# pcb_univ_3-2-_1-2_-x-rev2.net
KiCad netlist of a schematic drawn in EAGLE
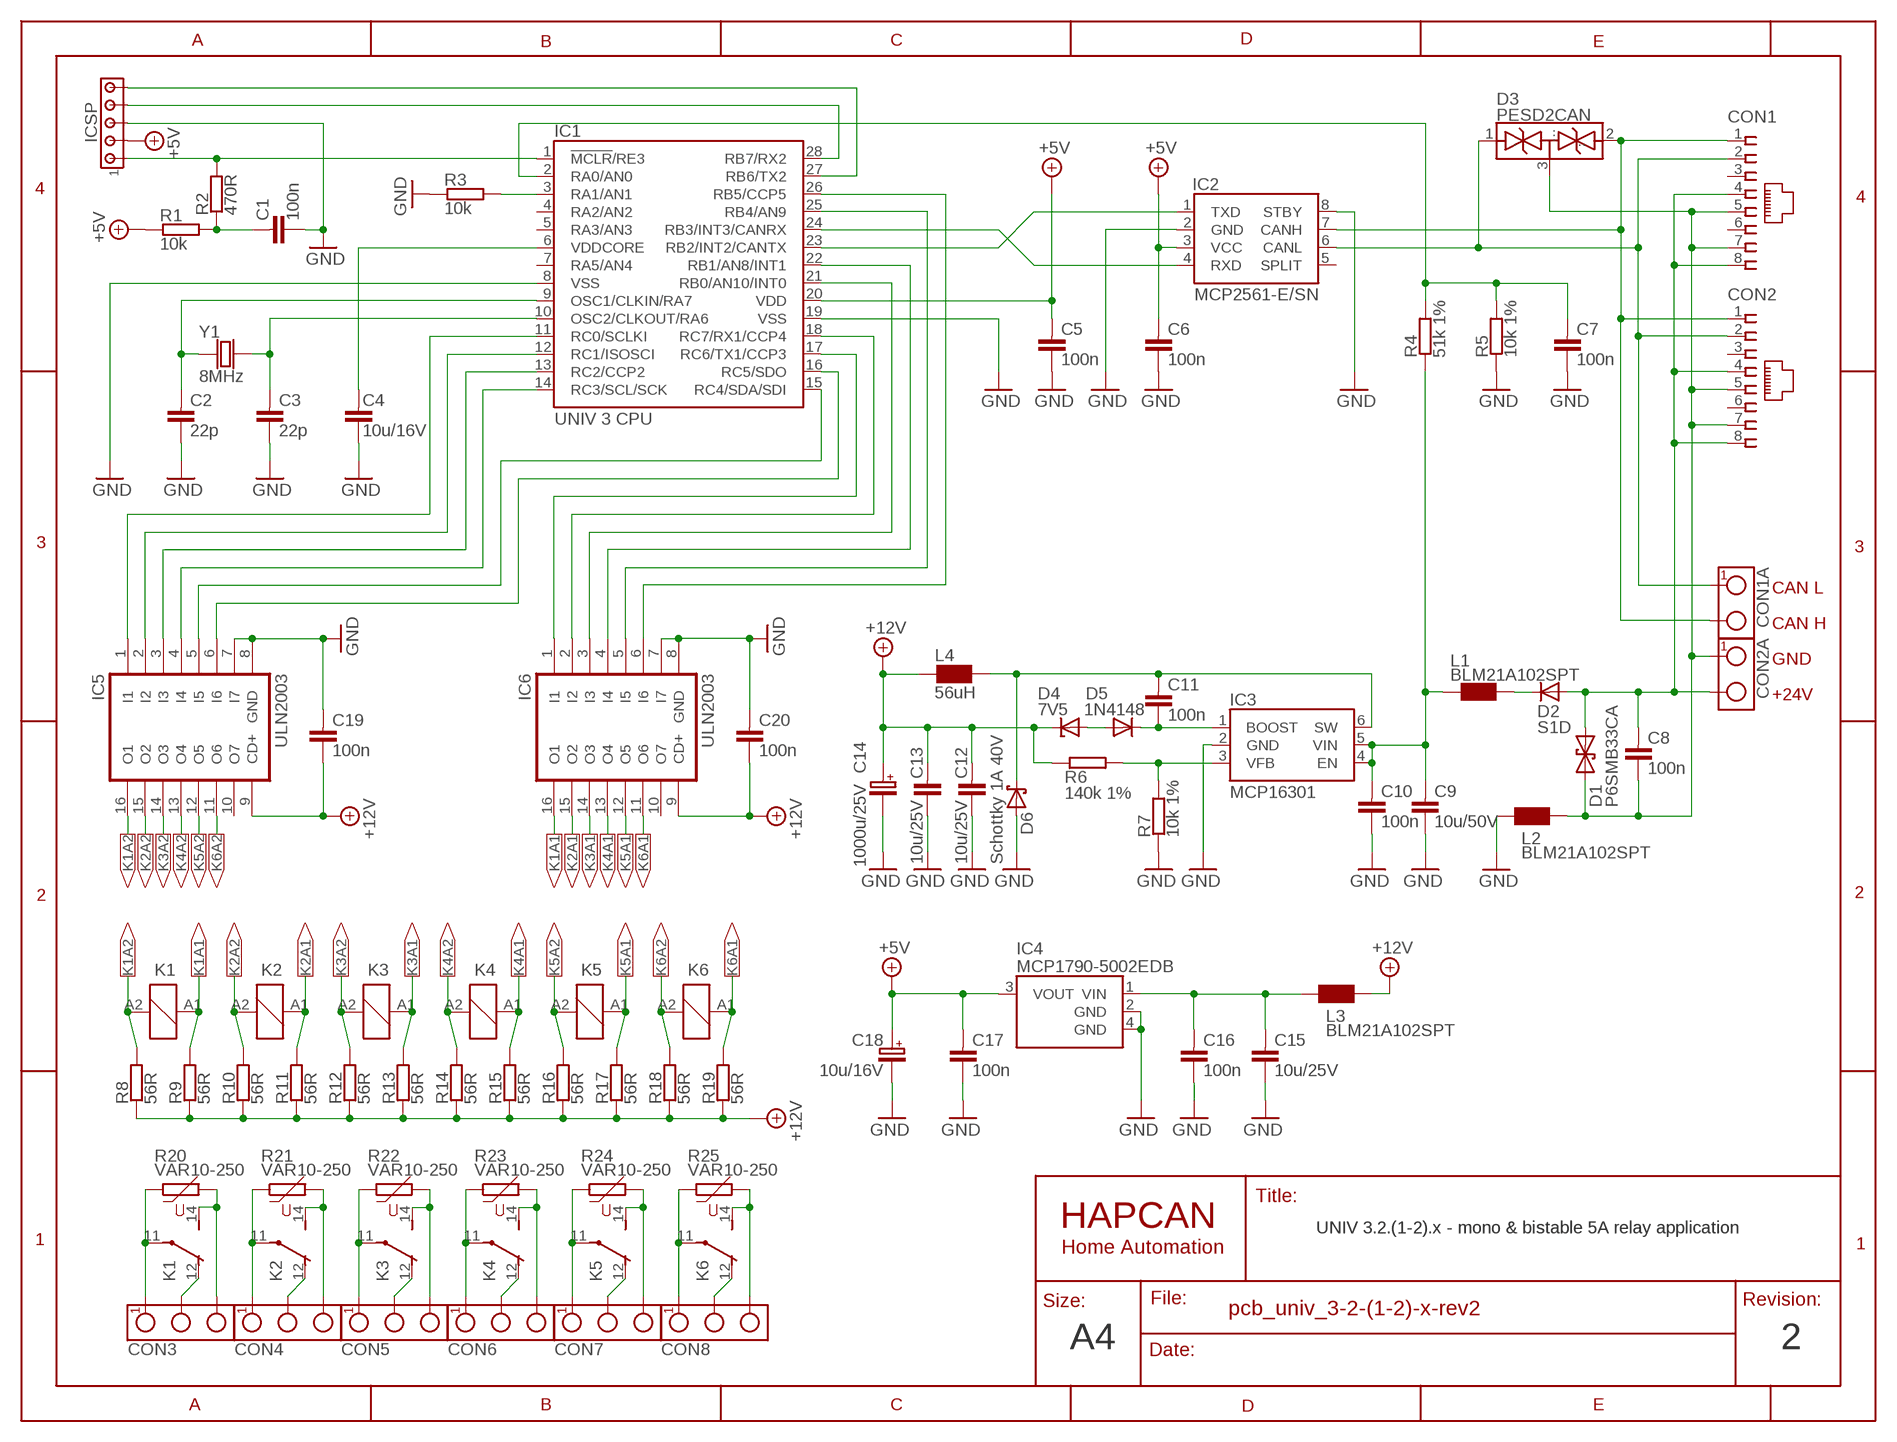
[diagram p0: schematic, sheet 1]

(export (version "E")
  (design (tool "Eeschema 10.0.6"))
  (components
    (comp (ref "C1")
      (value "100n")
      (footprint "eagle-import:0805")
      (libsource (lib "eagle-import") (part "CAPACITOR0805"))
    )
    (comp (ref "C2")
      (value "22p")
      (footprint "eagle-import:0805")
      (libsource (lib "eagle-import") (part "CAPACITOR0805"))
    )
    (comp (ref "C3")
      (value "22p")
      (footprint "eagle-import:0805")
      (libsource (lib "eagle-import") (part "CAPACITOR0805"))
    )
    (comp (ref "C4")
      (value "10u/16V")
      (footprint "eagle-import:0805")
      (libsource (lib "eagle-import") (part "CAPACITOR0805"))
    )
    (comp (ref "C5")
      (value "100n")
      (footprint "eagle-import:0805")
      (libsource (lib "eagle-import") (part "CAPACITOR0805"))
    )
    (comp (ref "C6")
      (value "100n")
      (footprint "eagle-import:0805")
      (libsource (lib "eagle-import") (part "CAPACITOR0805"))
    )
    (comp (ref "C7")
      (value "100n")
      (footprint "eagle-import:0805")
      (libsource (lib "eagle-import") (part "CAPACITOR0805"))
    )
    (comp (ref "C8")
      (value "100n")
      (footprint "eagle-import:0805")
      (libsource (lib "eagle-import") (part "CAPACITOR0805"))
    )
    (comp (ref "C9")
      (value "10u/50V")
      (footprint "eagle-import:1210")
      (libsource (lib "eagle-import") (part "CAPACITOR1210"))
    )
    (comp (ref "C10")
      (value "100n")
      (footprint "eagle-import:0805")
      (libsource (lib "eagle-import") (part "CAPACITOR0805"))
    )
    (comp (ref "C11")
      (value "100n")
      (footprint "eagle-import:0805")
      (libsource (lib "eagle-import") (part "CAPACITOR0805"))
    )
    (comp (ref "C12")
      (value "10u/25V")
      (footprint "eagle-import:1206")
      (libsource (lib "eagle-import") (part "CAPACITOR1206"))
    )
    (comp (ref "C13")
      (value "10u/25V")
      (footprint "eagle-import:1206")
      (libsource (lib "eagle-import") (part "CAPACITOR1206"))
    )
    (comp (ref "C14")
      (value "1000u/25V")
      (footprint "eagle-import:CAP-5X10.5")
      (libsource (lib "eagle-import") (part "CAPACITOR-POLARIZED-5X10.5"))
    )
    (comp (ref "C15")
      (value "10u/25V")
      (footprint "eagle-import:1206")
      (libsource (lib "eagle-import") (part "CAPACITOR1206"))
    )
    (comp (ref "C16")
      (value "100n")
      (footprint "eagle-import:0805")
      (libsource (lib "eagle-import") (part "CAPACITOR0805"))
    )
    (comp (ref "C17")
      (value "100n")
      (footprint "eagle-import:0805")
      (libsource (lib "eagle-import") (part "CAPACITOR0805"))
    )
    (comp (ref "C18")
      (value "10u/16V")
      (footprint "eagle-import:SMC_B")
      (libsource (lib "eagle-import") (part "CAPACITOR-POLARIZED-SMC_B"))
    )
    (comp (ref "C19")
      (value "100n")
      (footprint "eagle-import:0805")
      (libsource (lib "eagle-import") (part "CAPACITOR0805"))
    )
    (comp (ref "C20")
      (value "100n")
      (footprint "eagle-import:0805")
      (libsource (lib "eagle-import") (part "CAPACITOR0805"))
    )
    (comp (ref "CON1")
      (value "RJ45-SOCKET")
      (footprint "eagle-import:RJ45-PCB-SOCKET")
      (libsource (lib "eagle-import") (part "RJ45-SOCKET"))
    )
    (comp (ref "CON1A")
      (value "TERMINAL-2")
      (footprint "eagle-import:ARK2-5X10,5MM")
      (libsource (lib "eagle-import") (part "TERMINAL-2-5X10,5MM"))
    )
    (comp (ref "CON2")
      (value "RJ45-SOCKET")
      (footprint "eagle-import:RJ45-PCB-SOCKET")
      (libsource (lib "eagle-import") (part "RJ45-SOCKET"))
    )
    (comp (ref "CON2A")
      (value "TERMINAL-2")
      (footprint "eagle-import:ARK2-5X10,5MM")
      (libsource (lib "eagle-import") (part "TERMINAL-2-5X10,5MM"))
    )
    (comp (ref "CON3")
      (value "TERMINAL-3-5X10.5MM")
      (footprint "eagle-import:ARK3-5X10.5MM")
      (libsource (lib "eagle-import") (part "TERMINAL-3-5X10.5MM"))
    )
    (comp (ref "CON4")
      (value "TERMINAL-3-5X10.5MM")
      (footprint "eagle-import:ARK3-5X10.5MM")
      (libsource (lib "eagle-import") (part "TERMINAL-3-5X10.5MM"))
    )
    (comp (ref "CON5")
      (value "TERMINAL-3-5X10.5MM")
      (footprint "eagle-import:ARK3-5X10.5MM")
      (libsource (lib "eagle-import") (part "TERMINAL-3-5X10.5MM"))
    )
    (comp (ref "CON6")
      (value "TERMINAL-3-5X10.5MM")
      (footprint "eagle-import:ARK3-5X10.5MM")
      (libsource (lib "eagle-import") (part "TERMINAL-3-5X10.5MM"))
    )
    (comp (ref "CON7")
      (value "TERMINAL-3-5X10.5MM")
      (footprint "eagle-import:ARK3-5X10.5MM")
      (libsource (lib "eagle-import") (part "TERMINAL-3-5X10.5MM"))
    )
    (comp (ref "CON8")
      (value "TERMINAL-3-5X10.5MM")
      (footprint "eagle-import:ARK3-5X10.5MM")
      (libsource (lib "eagle-import") (part "TERMINAL-3-5X10.5MM"))
    )
    (comp (ref "D1")
      (value "P6SMB33CA")
      (footprint "eagle-import:DO-214_TRANSIL2")
      (libsource (lib "eagle-import") (part "DIODE_TRANSIL2"))
    )
    (comp (ref "D2")
      (value "S1D")
      (footprint "eagle-import:DO-214")
      (libsource (lib "eagle-import") (part "DIODE_DO-214"))
    )
    (comp (ref "D3")
      (value "PESD2CAN")
      (footprint "eagle-import:SOT-23")
      (libsource (lib "eagle-import") (part "PESD2CANSOT-23"))
    )
    (comp (ref "D4")
      (value "7V5")
      (footprint "eagle-import:SOD-80")
      (libsource (lib "eagle-import") (part "DIODE_ZENER_SOD-80"))
    )
    (comp (ref "D5")
      (value "1N4148")
      (footprint "eagle-import:0805")
      (libsource (lib "eagle-import") (part "DIODE_0805"))
    )
    (comp (ref "D6")
      (value "Schottky 1A 40V")
      (footprint "eagle-import:DO-214")
      (libsource (lib "eagle-import") (part "DIODE_TRANSIL1_DO214"))
    )
    (comp (ref "IC1")
      (value "UNIV 3 CPU")
      (footprint "eagle-import:UNIV3CPU")
      (libsource (lib "eagle-import") (part "UNIV3CPU-I/SO"))
    )
    (comp (ref "IC2")
      (value "MCP2561-E/SN")
      (footprint "eagle-import:SO-08")
      (libsource (lib "eagle-import") (part "MCP2561-E/SN"))
    )
    (comp (ref "IC3")
      (value "MCP16301")
      (footprint "eagle-import:SOT-23-6")
      (libsource (lib "eagle-import") (part "MCP16301SOT23-6"))
    )
    (comp (ref "IC4")
      (value "MCP1790-5002EDB")
      (footprint "eagle-import:SOT-223")
      (libsource (lib "eagle-import") (part "MCP1826SOT223-3"))
    )
    (comp (ref "IC5")
      (value "ULN2003")
      (footprint "eagle-import:SO-16")
      (libsource (lib "eagle-import") (part "ULN2003"))
    )
    (comp (ref "IC6")
      (value "ULN2003")
      (footprint "eagle-import:SO-16")
      (libsource (lib "eagle-import") (part "ULN2003"))
    )
    (comp (ref "ICSP")
      (value "HEADER5")
      (footprint "eagle-import:SIP-5")
      (libsource (lib "eagle-import") (part "HEADER5"))
    )
    (comp (ref "K1")
      (value "RELAY_PE")
      (footprint "eagle-import:RELAY_PE")
      (libsource (lib "eagle-import") (part "RELAY_PE"))
    )
    (comp (ref "K2")
      (value "RELAY_PE")
      (footprint "eagle-import:RELAY_PE")
      (libsource (lib "eagle-import") (part "RELAY_PE"))
    )
    (comp (ref "K3")
      (value "RELAY_PE")
      (footprint "eagle-import:RELAY_PE")
      (libsource (lib "eagle-import") (part "RELAY_PE"))
    )
    (comp (ref "K4")
      (value "RELAY_PE")
      (footprint "eagle-import:RELAY_PE")
      (libsource (lib "eagle-import") (part "RELAY_PE"))
    )
    (comp (ref "K5")
      (value "RELAY_PE")
      (footprint "eagle-import:RELAY_PE")
      (libsource (lib "eagle-import") (part "RELAY_PE"))
    )
    (comp (ref "K6")
      (value "RELAY_PE")
      (footprint "eagle-import:RELAY_PE")
      (libsource (lib "eagle-import") (part "RELAY_PE"))
    )
    (comp (ref "L1")
      (value "BLM21A102SPT")
      (footprint "eagle-import:0805")
      (libsource (lib "eagle-import") (part "CHOKE0805"))
    )
    (comp (ref "L2")
      (value "BLM21A102SPT")
      (footprint "eagle-import:0805")
      (libsource (lib "eagle-import") (part "CHOKE0805"))
    )
    (comp (ref "L3")
      (value "BLM21A102SPT")
      (footprint "eagle-import:0805")
      (libsource (lib "eagle-import") (part "CHOKE0805"))
    )
    (comp (ref "L4")
      (value "56uH")
      (footprint "eagle-import:CHOKE-DER0705")
      (libsource (lib "eagle-import") (part "CHOKEDER0705"))
    )
    (comp (ref "R1")
      (value "10k")
      (footprint "eagle-import:0805")
      (libsource (lib "eagle-import") (part "RESISTOR0805"))
    )
    (comp (ref "R2")
      (value "470R")
      (footprint "eagle-import:0805")
      (libsource (lib "eagle-import") (part "RESISTOR0805"))
    )
    (comp (ref "R3")
      (value "10k")
      (footprint "eagle-import:0805")
      (libsource (lib "eagle-import") (part "RESISTOR0805"))
    )
    (comp (ref "R4")
      (value "51k 1%")
      (footprint "eagle-import:0805")
      (libsource (lib "eagle-import") (part "RESISTOR0805"))
    )
    (comp (ref "R5")
      (value "10k 1%")
      (footprint "eagle-import:0805")
      (libsource (lib "eagle-import") (part "RESISTOR0805"))
    )
    (comp (ref "R6")
      (value "140k 1%")
      (footprint "eagle-import:0805")
      (libsource (lib "eagle-import") (part "RESISTOR0805"))
    )
    (comp (ref "R7")
      (value "10k 1%")
      (footprint "eagle-import:0805")
      (libsource (lib "eagle-import") (part "RESISTOR0805"))
    )
    (comp (ref "R8")
      (value "56R")
      (footprint "eagle-import:1206")
      (libsource (lib "eagle-import") (part "RESISTOR1206"))
    )
    (comp (ref "R9")
      (value "56R")
      (footprint "eagle-import:1206")
      (libsource (lib "eagle-import") (part "RESISTOR1206"))
    )
    (comp (ref "R10")
      (value "56R")
      (footprint "eagle-import:1206")
      (libsource (lib "eagle-import") (part "RESISTOR1206"))
    )
    (comp (ref "R11")
      (value "56R")
      (footprint "eagle-import:1206")
      (libsource (lib "eagle-import") (part "RESISTOR1206"))
    )
    (comp (ref "R12")
      (value "56R")
      (footprint "eagle-import:1206")
      (libsource (lib "eagle-import") (part "RESISTOR1206"))
    )
    (comp (ref "R13")
      (value "56R")
      (footprint "eagle-import:1206")
      (libsource (lib "eagle-import") (part "RESISTOR1206"))
    )
    (comp (ref "R14")
      (value "56R")
      (footprint "eagle-import:1206")
      (libsource (lib "eagle-import") (part "RESISTOR1206"))
    )
    (comp (ref "R15")
      (value "56R")
      (footprint "eagle-import:1206")
      (libsource (lib "eagle-import") (part "RESISTOR1206"))
    )
    (comp (ref "R16")
      (value "56R")
      (footprint "eagle-import:1206")
      (libsource (lib "eagle-import") (part "RESISTOR1206"))
    )
    (comp (ref "R17")
      (value "56R")
      (footprint "eagle-import:1206")
      (libsource (lib "eagle-import") (part "RESISTOR1206"))
    )
    (comp (ref "R18")
      (value "56R")
      (footprint "eagle-import:1206")
      (libsource (lib "eagle-import") (part "RESISTOR1206"))
    )
    (comp (ref "R19")
      (value "56R")
      (footprint "eagle-import:1206")
      (libsource (lib "eagle-import") (part "RESISTOR1206"))
    )
    (comp (ref "R20")
      (value "VAR10-250")
      (footprint "eagle-import:VARISTOR1")
      (libsource (lib "eagle-import") (part "VARISTOR7.5MM-1"))
    )
    (comp (ref "R21")
      (value "VAR10-250")
      (footprint "eagle-import:VARISTOR1")
      (libsource (lib "eagle-import") (part "VARISTOR7.5MM-1"))
    )
    (comp (ref "R22")
      (value "VAR10-250")
      (footprint "eagle-import:VARISTOR1")
      (libsource (lib "eagle-import") (part "VARISTOR7.5MM-1"))
    )
    (comp (ref "R23")
      (value "VAR10-250")
      (footprint "eagle-import:VARISTOR1")
      (libsource (lib "eagle-import") (part "VARISTOR7.5MM-1"))
    )
    (comp (ref "R24")
      (value "VAR10-250")
      (footprint "eagle-import:VARISTOR1")
      (libsource (lib "eagle-import") (part "VARISTOR7.5MM-1"))
    )
    (comp (ref "R25")
      (value "VAR10-250")
      (footprint "eagle-import:VARISTOR1")
      (libsource (lib "eagle-import") (part "VARISTOR7.5MM-1"))
    )
    (comp (ref "Y1")
      (value "8MHz")
      (footprint "eagle-import:CRYSTAL-HC49V")
      (libsource (lib "eagle-import") (part "CRYSTAL-HC49V"))
    )
  )
  (nets
    (net (code "1") (name "+5V") (class "Default")
      (node (ref "C17") (pin "1") (pinfunction "1_1") (pintype "passive"))
      (node (ref "C18") (pin "+") (pinfunction "1_+") (pintype "passive"))
      (node (ref "C5") (pin "1") (pinfunction "1_1") (pintype "passive"))
      (node (ref "C6") (pin "1") (pinfunction "1_1") (pintype "passive"))
      (node (ref "IC1") (pin "20") (pinfunction "VDD_20") (pintype "bidirectional"))
      (node (ref "IC2") (pin "3") (pinfunction "VCC_3") (pintype "bidirectional"))
      (node (ref "IC4") (pin "3") (pinfunction "VOUT_3") (pintype "bidirectional"))
      (node (ref "ICSP") (pin "2") (pinfunction "2_2") (pintype "passive"))
      (node (ref "R1") (pin "1") (pinfunction "1_1") (pintype "passive"))
    )
    (net (code "2") (name "+12V") (class "Default")
      (node (ref "C12") (pin "1") (pinfunction "1_1") (pintype "passive"))
      (node (ref "C13") (pin "1") (pinfunction "1_1") (pintype "passive"))
      (node (ref "C14") (pin "+") (pinfunction "1_+") (pintype "passive"))
      (node (ref "C19") (pin "2") (pinfunction "2_2") (pintype "passive"))
      (node (ref "C20") (pin "2") (pinfunction "2_2") (pintype "passive"))
      (node (ref "D4") (pin "C") (pinfunction "C_C") (pintype "passive"))
      (node (ref "IC5") (pin "9") (pinfunction "CD+_9") (pintype "passive"))
      (node (ref "IC6") (pin "9") (pinfunction "CD+_9") (pintype "passive"))
      (node (ref "L3") (pin "2") (pinfunction "2_2") (pintype "passive"))
      (node (ref "L4") (pin "1") (pinfunction "1_1") (pintype "passive"))
      (node (ref "R10") (pin "1") (pinfunction "1_1") (pintype "passive"))
      (node (ref "R11") (pin "1") (pinfunction "1_1") (pintype "passive"))
      (node (ref "R12") (pin "1") (pinfunction "1_1") (pintype "passive"))
      (node (ref "R13") (pin "1") (pinfunction "1_1") (pintype "passive"))
      (node (ref "R14") (pin "1") (pinfunction "1_1") (pintype "passive"))
      (node (ref "R15") (pin "1") (pinfunction "1_1") (pintype "passive"))
      (node (ref "R16") (pin "1") (pinfunction "1_1") (pintype "passive"))
      (node (ref "R17") (pin "1") (pinfunction "1_1") (pintype "passive"))
      (node (ref "R18") (pin "1") (pinfunction "1_1") (pintype "passive"))
      (node (ref "R19") (pin "1") (pinfunction "1_1") (pintype "passive"))
      (node (ref "R6") (pin "1") (pinfunction "1_1") (pintype "passive"))
      (node (ref "R8") (pin "1") (pinfunction "1_1") (pintype "passive"))
      (node (ref "R9") (pin "1") (pinfunction "1_1") (pintype "passive"))
    )
    (net (code "3") (name "/K1A1") (class "Default")
      (node (ref "IC6") (pin "16") (pinfunction "O1_16") (pintype "open_collector"))
      (node (ref "K1") (pin "A1") (pinfunction "1_A1") (pintype "passive"))
      (node (ref "R9") (pin "2") (pinfunction "2_2") (pintype "passive"))
    )
    (net (code "4") (name "/K1A2") (class "Default")
      (node (ref "IC5") (pin "16") (pinfunction "O1_16") (pintype "open_collector"))
      (node (ref "K1") (pin "A2") (pinfunction "2_A2") (pintype "passive"))
      (node (ref "R8") (pin "2") (pinfunction "2_2") (pintype "passive"))
    )
    (net (code "5") (name "/K2A1") (class "Default")
      (node (ref "IC6") (pin "15") (pinfunction "O2_15") (pintype "open_collector"))
      (node (ref "K2") (pin "A1") (pinfunction "1_A1") (pintype "passive"))
      (node (ref "R11") (pin "2") (pinfunction "2_2") (pintype "passive"))
    )
    (net (code "6") (name "/K2A2") (class "Default")
      (node (ref "IC5") (pin "15") (pinfunction "O2_15") (pintype "open_collector"))
      (node (ref "K2") (pin "A2") (pinfunction "2_A2") (pintype "passive"))
      (node (ref "R10") (pin "2") (pinfunction "2_2") (pintype "passive"))
    )
    (net (code "7") (name "/K3A1") (class "Default")
      (node (ref "IC6") (pin "14") (pinfunction "O3_14") (pintype "open_collector"))
      (node (ref "K3") (pin "A1") (pinfunction "1_A1") (pintype "passive"))
      (node (ref "R13") (pin "2") (pinfunction "2_2") (pintype "passive"))
    )
    (net (code "8") (name "/K3A2") (class "Default")
      (node (ref "IC5") (pin "14") (pinfunction "O3_14") (pintype "open_collector"))
      (node (ref "K3") (pin "A2") (pinfunction "2_A2") (pintype "passive"))
      (node (ref "R12") (pin "2") (pinfunction "2_2") (pintype "passive"))
    )
    (net (code "9") (name "/K4A1") (class "Default")
      (node (ref "IC6") (pin "13") (pinfunction "O4_13") (pintype "open_collector"))
      (node (ref "K4") (pin "A1") (pinfunction "1_A1") (pintype "passive"))
      (node (ref "R15") (pin "2") (pinfunction "2_2") (pintype "passive"))
    )
    (net (code "10") (name "/K4A2") (class "Default")
      (node (ref "IC5") (pin "13") (pinfunction "O4_13") (pintype "open_collector"))
      (node (ref "K4") (pin "A2") (pinfunction "2_A2") (pintype "passive"))
      (node (ref "R14") (pin "2") (pinfunction "2_2") (pintype "passive"))
    )
    (net (code "11") (name "/K5A1") (class "Default")
      (node (ref "IC6") (pin "12") (pinfunction "O5_12") (pintype "open_collector"))
      (node (ref "K5") (pin "A1") (pinfunction "1_A1") (pintype "passive"))
      (node (ref "R17") (pin "2") (pinfunction "2_2") (pintype "passive"))
    )
    (net (code "12") (name "/K5A2") (class "Default")
      (node (ref "IC5") (pin "12") (pinfunction "O5_12") (pintype "open_collector"))
      (node (ref "K5") (pin "A2") (pinfunction "2_A2") (pintype "passive"))
      (node (ref "R16") (pin "2") (pinfunction "2_2") (pintype "passive"))
    )
    (net (code "13") (name "/K6A1") (class "Default")
      (node (ref "IC6") (pin "11") (pinfunction "O6_11") (pintype "open_collector"))
      (node (ref "K6") (pin "A1") (pinfunction "1_A1") (pintype "passive"))
      (node (ref "R19") (pin "2") (pinfunction "2_2") (pintype "passive"))
    )
    (net (code "14") (name "/K6A2") (class "Default")
      (node (ref "IC5") (pin "11") (pinfunction "O6_11") (pintype "open_collector"))
      (node (ref "K6") (pin "A2") (pinfunction "2_A2") (pintype "passive"))
      (node (ref "R18") (pin "2") (pinfunction "2_2") (pintype "passive"))
    )
    (net (code "15") (name "GND") (class "Default")
      (node (ref "C1") (pin "2") (pinfunction "2_2") (pintype "passive"))
      (node (ref "C10") (pin "2") (pinfunction "2_2") (pintype "passive"))
      (node (ref "C12") (pin "2") (pinfunction "2_2") (pintype "passive"))
      (node (ref "C13") (pin "2") (pinfunction "2_2") (pintype "passive"))
      (node (ref "C14") (pin "-") (pinfunction "2_-") (pintype "passive"))
      (node (ref "C15") (pin "2") (pinfunction "2_2") (pintype "passive"))
      (node (ref "C16") (pin "2") (pinfunction "2_2") (pintype "passive"))
      (node (ref "C17") (pin "2") (pinfunction "2_2") (pintype "passive"))
      (node (ref "C18") (pin "-") (pinfunction "2_-") (pintype "passive"))
      (node (ref "C19") (pin "1") (pinfunction "1_1") (pintype "passive"))
      (node (ref "C2") (pin "2") (pinfunction "2_2") (pintype "passive"))
      (node (ref "C20") (pin "1") (pinfunction "1_1") (pintype "passive"))
      (node (ref "C3") (pin "2") (pinfunction "2_2") (pintype "passive"))
      (node (ref "C4") (pin "2") (pinfunction "2_2") (pintype "passive"))
      (node (ref "C5") (pin "2") (pinfunction "2_2") (pintype "passive"))
      (node (ref "C6") (pin "2") (pinfunction "2_2") (pintype "passive"))
      (node (ref "C7") (pin "2") (pinfunction "2_2") (pintype "passive"))
      (node (ref "C9") (pin "2") (pinfunction "2_2") (pintype "passive"))
      (node (ref "D6") (pin "A") (pinfunction "A_A") (pintype "passive"))
      (node (ref "IC1") (pin "19") (pinfunction "VSS_19") (pintype "bidirectional"))
      (node (ref "IC1") (pin "8") (pinfunction "VSS_8") (pintype "bidirectional"))
      (node (ref "IC2") (pin "2") (pinfunction "GND_2") (pintype "bidirectional"))
      (node (ref "IC2") (pin "8") (pinfunction "STBY_8") (pintype "bidirectional"))
      (node (ref "IC3") (pin "2") (pinfunction "GND_2") (pintype "bidirectional"))
      (node (ref "IC4") (pin "2") (pinfunction "GND_2") (pintype "bidirectional"))
      (node (ref "IC4") (pin "4") (pinfunction "GND_4") (pintype "bidirectional"))
      (node (ref "IC5") (pin "7") (pinfunction "I7_7") (pintype "input"))
      (node (ref "IC5") (pin "8") (pinfunction "GND_8") (pintype "power_in"))
      (node (ref "IC6") (pin "7") (pinfunction "I7_7") (pintype "input"))
      (node (ref "IC6") (pin "8") (pinfunction "GND_8") (pintype "power_in"))
      (node (ref "ICSP") (pin "3") (pinfunction "3_3") (pintype "passive"))
      (node (ref "L2") (pin "1") (pinfunction "1_1") (pintype "passive"))
      (node (ref "R3") (pin "1") (pinfunction "1_1") (pintype "passive"))
      (node (ref "R5") (pin "1") (pinfunction "1_1") (pintype "passive"))
      (node (ref "R7") (pin "1") (pinfunction "1_1") (pintype "passive"))
    )
    (net (code "16") (name "Net-(C1-Pad1)") (class "Default")
      (node (ref "C1") (pin "1") (pinfunction "1_1") (pintype "passive"))
      (node (ref "R1") (pin "2") (pinfunction "2_2") (pintype "passive"))
      (node (ref "R2") (pin "1") (pinfunction "1_1") (pintype "passive"))
    )
    (net (code "17") (name "Net-(D1-1)") (class "Default")
      (node (ref "C8") (pin "2") (pinfunction "2_2") (pintype "passive"))
      (node (ref "CON1") (pin "5") (pinfunction "5_5") (pintype "passive"))
      (node (ref "CON1") (pin "7") (pinfunction "7_7") (pintype "passive"))
      (node (ref "CON2") (pin "5") (pinfunction "5_5") (pintype "passive"))
      (node (ref "CON2") (pin "7") (pinfunction "7_7") (pintype "passive"))
      (node (ref "CON2A") (pin "1") (pinfunction "1_1") (pintype "passive"))
      (node (ref "D1") (pin "A") (pinfunction "1_A") (pintype "passive"))
      (node (ref "D3") (pin "3") (pinfunction "..._3") (pintype "bidirectional"))
      (node (ref "L2") (pin "2") (pinfunction "2_2") (pintype "passive"))
    )
    (net (code "18") (name "Net-(D1-2)") (class "Default")
      (node (ref "C8") (pin "1") (pinfunction "1_1") (pintype "passive"))
      (node (ref "CON1") (pin "4") (pinfunction "4_4") (pintype "passive"))
      (node (ref "CON1") (pin "8") (pinfunction "8_8") (pintype "passive"))
      (node (ref "CON2") (pin "4") (pinfunction "4_4") (pintype "passive"))
      (node (ref "CON2") (pin "8") (pinfunction "8_8") (pintype "passive"))
      (node (ref "CON2A") (pin "2") (pinfunction "2_2") (pintype "passive"))
      (node (ref "D1") (pin "C") (pinfunction "2_C") (pintype "passive"))
      (node (ref "D2") (pin "A") (pinfunction "A_A") (pintype "passive"))
    )
    (net (code "19") (name "Net-(D2-PadC)") (class "Default")
      (node (ref "D2") (pin "C") (pinfunction "C_C") (pintype "passive"))
      (node (ref "L1") (pin "2") (pinfunction "2_2") (pintype "passive"))
    )
    (net (code "20") (name "Net-(D3-.)") (class "Default")
      (node (ref "CON1") (pin "2") (pinfunction "2_2") (pintype "passive"))
      (node (ref "CON1A") (pin "1") (pinfunction "1_1") (pintype "passive"))
      (node (ref "CON2") (pin "2") (pinfunction "2_2") (pintype "passive"))
      (node (ref "D3") (pin "1") (pinfunction "._1") (pintype "bidirectional"))
      (node (ref "IC2") (pin "6") (pinfunction "CANL_6") (pintype "bidirectional"))
    )
    (net (code "21") (name "Net-(D3-..)") (class "Default")
      (node (ref "CON1") (pin "1") (pinfunction "1_1") (pintype "passive"))
      (node (ref "CON1A") (pin "2") (pinfunction "2_2") (pintype "passive"))
      (node (ref "CON2") (pin "1") (pinfunction "1_1") (pintype "passive"))
      (node (ref "D3") (pin "2") (pinfunction ".._2") (pintype "bidirectional"))
      (node (ref "IC2") (pin "7") (pinfunction "CANH_7") (pintype "bidirectional"))
    )
    (net (code "22") (name "Net-(D5-A)") (class "Default")
      (node (ref "D4") (pin "A") (pinfunction "A_A") (pintype "passive"))
      (node (ref "D5") (pin "2") (pinfunction "A_2") (pintype "passive"))
    )
    (net (code "23") (name "Net-(D5-C)") (class "Default")
      (node (ref "C11") (pin "2") (pinfunction "2_2") (pintype "passive"))
      (node (ref "D5") (pin "1") (pinfunction "C_1") (pintype "passive"))
      (node (ref "IC3") (pin "1") (pinfunction "BOOST_1") (pintype "bidirectional"))
    )
    (net (code "24") (name "Net-(IC1-OSC1{slash}CLKIN{slash}RA7)") (class "Default")
      (node (ref "C2") (pin "1") (pinfunction "1_1") (pintype "passive"))
      (node (ref "IC1") (pin "9") (pinfunction "OSC1/CLKIN/RA7_9") (pintype "bidirectional"))
      (node (ref "Y1") (pin "1") (pinfunction "1_1") (pintype "passive"))
    )
    (net (code "25") (name "Net-(IC1-OSC2{slash}CLKOUT{slash}RA6)") (class "Default")
      (node (ref "C3") (pin "1") (pinfunction "1_1") (pintype "passive"))
      (node (ref "IC1") (pin "10") (pinfunction "OSC2/CLKOUT/RA6_10") (pintype "bidirectional"))
      (node (ref "Y1") (pin "2") (pinfunction "2_2") (pintype "passive"))
    )
    (net (code "26") (name "Net-(IC1-RA0{slash}AN0)") (class "Default")
      (node (ref "C7") (pin "1") (pinfunction "1_1") (pintype "passive"))
      (node (ref "IC1") (pin "2") (pinfunction "RA0/AN0_2") (pintype "bidirectional"))
      (node (ref "R4") (pin "2") (pinfunction "2_2") (pintype "passive"))
      (node (ref "R5") (pin "2") (pinfunction "2_2") (pintype "passive"))
    )
    (net (code "27") (name "Net-(IC1-RA1{slash}AN1)") (class "Default")
      (node (ref "IC1") (pin "3") (pinfunction "RA1/AN1_3") (pintype "bidirectional"))
      (node (ref "R3") (pin "2") (pinfunction "2_2") (pintype "passive"))
    )
    (net (code "28") (name "Net-(IC1-RB0{slash}AN10{slash}INT0)") (class "Default")
      (node (ref "IC1") (pin "21") (pinfunction "RB0/AN10/INT0_21") (pintype "bidirectional"))
      (node (ref "IC6") (pin "3") (pinfunction "I3_3") (pintype "input"))
    )
    (net (code "29") (name "Net-(IC1-RB1{slash}AN8{slash}INT1)") (class "Default")
      (node (ref "IC1") (pin "22") (pinfunction "RB1/AN8/INT1_22") (pintype "bidirectional"))
      (node (ref "IC6") (pin "4") (pinfunction "I4_4") (pintype "input"))
    )
    (net (code "30") (name "Net-(IC1-RB2{slash}INT2{slash}CANTX)") (class "Default")
      (node (ref "IC1") (pin "23") (pinfunction "RB2/INT2/CANTX_23") (pintype "bidirectional"))
      (node (ref "IC2") (pin "1") (pinfunction "TXD_1") (pintype "bidirectional"))
    )
    (net (code "31") (name "Net-(IC1-RB3{slash}INT3{slash}CANRX)") (class "Default")
      (node (ref "IC1") (pin "24") (pinfunction "RB3/INT3/CANRX_24") (pintype "bidirectional"))
      (node (ref "IC2") (pin "4") (pinfunction "RXD_4") (pintype "bidirectional"))
    )
    (net (code "32") (name "Net-(IC1-RB4{slash}AN9)") (class "Default")
      (node (ref "IC1") (pin "25") (pinfunction "RB4/AN9_25") (pintype "bidirectional"))
      (node (ref "IC6") (pin "5") (pinfunction "I5_5") (pintype "input"))
    )
    (net (code "33") (name "Net-(IC1-RB5{slash}CCP5)") (class "Default")
      (node (ref "IC1") (pin "26") (pinfunction "RB5/CCP5_26") (pintype "bidirectional"))
      (node (ref "IC6") (pin "6") (pinfunction "I6_6") (pintype "input"))
    )
    (net (code "34") (name "Net-(IC1-RB6{slash}TX2)") (class "Default")
      (node (ref "IC1") (pin "27") (pinfunction "RB6/TX2_27") (pintype "bidirectional"))
      (node (ref "ICSP") (pin "5") (pinfunction "5_5") (pintype "passive"))
    )
    (net (code "35") (name "Net-(IC1-RB7{slash}RX2)") (class "Default")
      (node (ref "IC1") (pin "28") (pinfunction "RB7/RX2_28") (pintype "bidirectional"))
      (node (ref "ICSP") (pin "4") (pinfunction "4_4") (pintype "passive"))
    )
    (net (code "36") (name "Net-(IC1-RC0{slash}SCLKI)") (class "Default")
      (node (ref "IC1") (pin "11") (pinfunction "RC0/SCLKI_11") (pintype "bidirectional"))
      (node (ref "IC5") (pin "1") (pinfunction "I1_1") (pintype "input"))
    )
    (net (code "37") (name "Net-(IC1-RC1{slash}ISOSCI)") (class "Default")
      (node (ref "IC1") (pin "12") (pinfunction "RC1/ISOSCI_12") (pintype "bidirectional"))
      (node (ref "IC5") (pin "2") (pinfunction "I2_2") (pintype "input"))
    )
    (net (code "38") (name "Net-(IC1-RC2{slash}CCP2)") (class "Default")
      (node (ref "IC1") (pin "13") (pinfunction "RC2/CCP2_13") (pintype "bidirectional"))
      (node (ref "IC5") (pin "3") (pinfunction "I3_3") (pintype "input"))
    )
    (net (code "39") (name "Net-(IC1-RC3{slash}SCL{slash}SCK)") (class "Default")
      (node (ref "IC1") (pin "14") (pinfunction "RC3/SCL/SCK_14") (pintype "bidirectional"))
      (node (ref "IC5") (pin "4") (pinfunction "I4_4") (pintype "input"))
    )
    (net (code "40") (name "Net-(IC1-RC4{slash}SDA{slash}SDI)") (class "Default")
      (node (ref "IC1") (pin "15") (pinfunction "RC4/SDA/SDI_15") (pintype "bidirectional"))
      (node (ref "IC5") (pin "5") (pinfunction "I5_5") (pintype "input"))
    )
    (net (code "41") (name "Net-(IC1-RC5{slash}SDO)") (class "Default")
      (node (ref "IC1") (pin "16") (pinfunction "RC5/SDO_16") (pintype "bidirectional"))
      (node (ref "IC5") (pin "6") (pinfunction "I6_6") (pintype "input"))
    )
    (net (code "42") (name "Net-(IC1-RC6{slash}TX1{slash}CCP3)") (class "Default")
      (node (ref "IC1") (pin "17") (pinfunction "RC6/TX1/CCP3_17") (pintype "bidirectional"))
      (node (ref "IC6") (pin "1") (pinfunction "I1_1") (pintype "input"))
    )
    (net (code "43") (name "Net-(IC1-RC7{slash}RX1{slash}CCP4)") (class "Default")
      (node (ref "IC1") (pin "18") (pinfunction "RC7/RX1/CCP4_18") (pintype "bidirectional"))
      (node (ref "IC6") (pin "2") (pinfunction "I2_2") (pintype "input"))
    )
    (net (code "44") (name "Net-(IC1-VDDCORE)") (class "Default")
      (node (ref "C4") (pin "1") (pinfunction "1_1") (pintype "passive"))
      (node (ref "IC1") (pin "6") (pinfunction "VDDCORE_6") (pintype "bidirectional"))
    )
    (net (code "45") (name "Net-(IC1-~{MCLR}{slash}RE3)") (class "Default")
      (node (ref "IC1") (pin "1") (pinfunction "~{MCLR}/RE3_1") (pintype "bidirectional"))
      (node (ref "ICSP") (pin "1") (pinfunction "1_1") (pintype "passive"))
      (node (ref "R2") (pin "2") (pinfunction "2_2") (pintype "passive"))
    )
    (net (code "46") (name "Net-(IC3-EN)") (class "Default")
      (node (ref "C10") (pin "1") (pinfunction "1_1") (pintype "passive"))
      (node (ref "C9") (pin "1") (pinfunction "1_1") (pintype "passive"))
      (node (ref "IC3") (pin "4") (pinfunction "EN_4") (pintype "bidirectional"))
      (node (ref "IC3") (pin "5") (pinfunction "VIN_5") (pintype "bidirectional"))
      (node (ref "L1") (pin "1") (pinfunction "1_1") (pintype "passive"))
      (node (ref "R4") (pin "1") (pinfunction "1_1") (pintype "passive"))
    )
    (net (code "47") (name "Net-(IC3-SW)") (class "Default")
      (node (ref "C11") (pin "1") (pinfunction "1_1") (pintype "passive"))
      (node (ref "D6") (pin "C") (pinfunction "C_C") (pintype "passive"))
      (node (ref "IC3") (pin "6") (pinfunction "SW_6") (pintype "bidirectional"))
      (node (ref "L4") (pin "2") (pinfunction "2_2") (pintype "passive"))
    )
    (net (code "48") (name "Net-(IC3-VFB)") (class "Default")
      (node (ref "IC3") (pin "3") (pinfunction "VFB_3") (pintype "bidirectional"))
      (node (ref "R6") (pin "2") (pinfunction "2_2") (pintype "passive"))
      (node (ref "R7") (pin "2") (pinfunction "2_2") (pintype "passive"))
    )
    (net (code "49") (name "Net-(IC4-VIN)") (class "Default")
      (node (ref "C15") (pin "1") (pinfunction "1_1") (pintype "passive"))
      (node (ref "C16") (pin "1") (pinfunction "1_1") (pintype "passive"))
      (node (ref "IC4") (pin "1") (pinfunction "VIN_1") (pintype "bidirectional"))
      (node (ref "L3") (pin "1") (pinfunction "1_1") (pintype "passive"))
    )
    (net (code "50") (name "Net-(K1B-COM)") (class "Default")
      (node (ref "CON3") (pin "1") (pinfunction "1_1") (pintype "passive"))
      (node (ref "K1") (pin "11") (pinfunction "COM_11") (pintype "passive"))
      (node (ref "R20") (pin "1") (pinfunction "1_1") (pintype "passive"))
    )
    (net (code "51") (name "Net-(K1B-NC)") (class "Default")
      (node (ref "CON3") (pin "2") (pinfunction "2_2") (pintype "passive"))
      (node (ref "K1") (pin "12") (pinfunction "NC_12") (pintype "passive"))
    )
    (net (code "52") (name "Net-(K1B-NO)") (class "Default")
      (node (ref "CON3") (pin "3") (pinfunction "3_3") (pintype "passive"))
      (node (ref "K1") (pin "14") (pinfunction "NO_14") (pintype "passive"))
      (node (ref "R20") (pin "2") (pinfunction "2_2") (pintype "passive"))
    )
    (net (code "53") (name "Net-(K2B-COM)") (class "Default")
      (node (ref "CON4") (pin "1") (pinfunction "1_1") (pintype "passive"))
      (node (ref "K2") (pin "11") (pinfunction "COM_11") (pintype "passive"))
      (node (ref "R21") (pin "1") (pinfunction "1_1") (pintype "passive"))
    )
    (net (code "54") (name "Net-(K2B-NC)") (class "Default")
      (node (ref "CON4") (pin "2") (pinfunction "2_2") (pintype "passive"))
      (node (ref "K2") (pin "12") (pinfunction "NC_12") (pintype "passive"))
    )
    (net (code "55") (name "Net-(K2B-NO)") (class "Default")
      (node (ref "CON4") (pin "3") (pinfunction "3_3") (pintype "passive"))
      (node (ref "K2") (pin "14") (pinfunction "NO_14") (pintype "passive"))
      (node (ref "R21") (pin "2") (pinfunction "2_2") (pintype "passive"))
    )
    (net (code "56") (name "Net-(K3B-COM)") (class "Default")
      (node (ref "CON5") (pin "1") (pinfunction "1_1") (pintype "passive"))
      (node (ref "K3") (pin "11") (pinfunction "COM_11") (pintype "passive"))
      (node (ref "R22") (pin "1") (pinfunction "1_1") (pintype "passive"))
    )
    (net (code "57") (name "Net-(K3B-NC)") (class "Default")
      (node (ref "CON5") (pin "2") (pinfunction "2_2") (pintype "passive"))
      (node (ref "K3") (pin "12") (pinfunction "NC_12") (pintype "passive"))
    )
    (net (code "58") (name "Net-(K3B-NO)") (class "Default")
      (node (ref "CON5") (pin "3") (pinfunction "3_3") (pintype "passive"))
      (node (ref "K3") (pin "14") (pinfunction "NO_14") (pintype "passive"))
      (node (ref "R22") (pin "2") (pinfunction "2_2") (pintype "passive"))
    )
    (net (code "59") (name "Net-(K4B-COM)") (class "Default")
      (node (ref "CON6") (pin "1") (pinfunction "1_1") (pintype "passive"))
      (node (ref "K4") (pin "11") (pinfunction "COM_11") (pintype "passive"))
      (node (ref "R23") (pin "1") (pinfunction "1_1") (pintype "passive"))
    )
    (net (code "60") (name "Net-(K4B-NC)") (class "Default")
      (node (ref "CON6") (pin "2") (pinfunction "2_2") (pintype "passive"))
      (node (ref "K4") (pin "12") (pinfunction "NC_12") (pintype "passive"))
    )
    (net (code "61") (name "Net-(K4B-NO)") (class "Default")
      (node (ref "CON6") (pin "3") (pinfunction "3_3") (pintype "passive"))
      (node (ref "K4") (pin "14") (pinfunction "NO_14") (pintype "passive"))
      (node (ref "R23") (pin "2") (pinfunction "2_2") (pintype "passive"))
    )
    (net (code "62") (name "Net-(K5B-COM)") (class "Default")
      (node (ref "CON7") (pin "1") (pinfunction "1_1") (pintype "passive"))
      (node (ref "K5") (pin "11") (pinfunction "COM_11") (pintype "passive"))
      (node (ref "R24") (pin "1") (pinfunction "1_1") (pintype "passive"))
    )
    (net (code "63") (name "Net-(K5B-NC)") (class "Default")
      (node (ref "CON7") (pin "2") (pinfunction "2_2") (pintype "passive"))
      (node (ref "K5") (pin "12") (pinfunction "NC_12") (pintype "passive"))
    )
    (net (code "64") (name "Net-(K5B-NO)") (class "Default")
      (node (ref "CON7") (pin "3") (pinfunction "3_3") (pintype "passive"))
      (node (ref "K5") (pin "14") (pinfunction "NO_14") (pintype "passive"))
      (node (ref "R24") (pin "2") (pinfunction "2_2") (pintype "passive"))
    )
    (net (code "65") (name "Net-(K6B-COM)") (class "Default")
      (node (ref "CON8") (pin "1") (pinfunction "1_1") (pintype "passive"))
      (node (ref "K6") (pin "11") (pinfunction "COM_11") (pintype "passive"))
      (node (ref "R25") (pin "1") (pinfunction "1_1") (pintype "passive"))
    )
    (net (code "66") (name "Net-(K6B-NC)") (class "Default")
      (node (ref "CON8") (pin "2") (pinfunction "2_2") (pintype "passive"))
      (node (ref "K6") (pin "12") (pinfunction "NC_12") (pintype "passive"))
    )
    (net (code "67") (name "Net-(K6B-NO)") (class "Default")
      (node (ref "CON8") (pin "3") (pinfunction "3_3") (pintype "passive"))
      (node (ref "K6") (pin "14") (pinfunction "NO_14") (pintype "passive"))
      (node (ref "R25") (pin "2") (pinfunction "2_2") (pintype "passive"))
    )
    (net (code "68") (name "unconnected-(CON1-Pad3)") (class "Default")
      (node (ref "CON1") (pin "3") (pinfunction "3_3") (pintype "passive"))
    )
    (net (code "69") (name "unconnected-(CON1-Pad6)") (class "Default")
      (node (ref "CON1") (pin "6") (pinfunction "6_6") (pintype "passive"))
    )
    (net (code "70") (name "unconnected-(CON2-Pad3)") (class "Default")
      (node (ref "CON2") (pin "3") (pinfunction "3_3") (pintype "passive"))
    )
    (net (code "71") (name "unconnected-(CON2-Pad6)") (class "Default")
      (node (ref "CON2") (pin "6") (pinfunction "6_6") (pintype "passive"))
    )
    (net (code "72") (name "unconnected-(IC1-RA2{slash}AN2-Pad4)") (class "Default")
      (node (ref "IC1") (pin "4") (pinfunction "RA2/AN2_4") (pintype "bidirectional"))
    )
    (net (code "73") (name "unconnected-(IC1-RA3{slash}AN3-Pad5)") (class "Default")
      (node (ref "IC1") (pin "5") (pinfunction "RA3/AN3_5") (pintype "bidirectional"))
    )
    (net (code "74") (name "unconnected-(IC1-RA5{slash}AN4-Pad7)") (class "Default")
      (node (ref "IC1") (pin "7") (pinfunction "RA5/AN4_7") (pintype "bidirectional"))
    )
    (net (code "75") (name "unconnected-(IC2-SPLIT-Pad5)") (class "Default")
      (node (ref "IC2") (pin "5") (pinfunction "SPLIT_5") (pintype "bidirectional"))
    )
    (net (code "76") (name "unconnected-(IC5-O7-Pad10)") (class "Default")
      (node (ref "IC5") (pin "10") (pinfunction "O7_10") (pintype "open_collector"))
    )
    (net (code "77") (name "unconnected-(IC6-O7-Pad10)") (class "Default")
      (node (ref "IC6") (pin "10") (pinfunction "O7_10") (pintype "open_collector"))
    )
  )
)
